# Bypass.net
KiCad netlist of a schematic drawn in Altium Designer
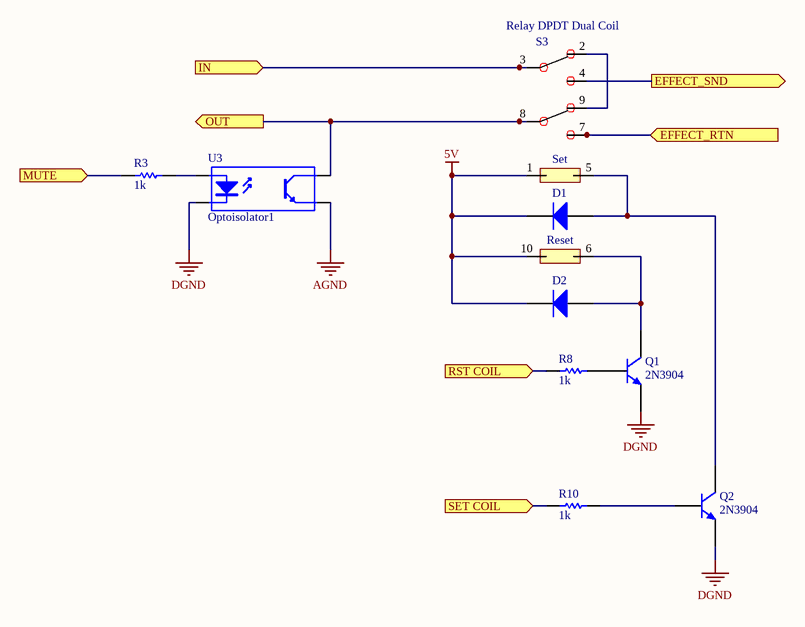
[diagram p0: Bypass.SchDoc]

(export (version "E")
  (design (tool "Eeschema 10.0.6"))
  (components
    (comp (ref "D1")
      (value "Diode 1N4148")
      (footprint "DO-35")
      (description "High Conductance Fast Diode")
      (fields (field (name "PUBLISHER") "Altium Limited"))
      (libsource (lib "Miscellaneous Devices") (part "Diode 1N4148"))
    )
    (comp (ref "D2")
      (value "Diode 1N4148")
      (footprint "DO-35")
      (description "High Conductance Fast Diode")
      (fields (field (name "PUBLISHER") "Altium Limited"))
      (libsource (lib "Miscellaneous Devices") (part "Diode 1N4148"))
    )
    (comp (ref "Q1")
      (value "2N3904")
      (footprint "TO-92A")
      (description "NPN General Purpose Amplifier")
      (fields (field (name "PUBLISHER") "Altium Limited"))
      (libsource (lib "Miscellaneous Devices") (part "2N3904"))
    )
    (comp (ref "Q2")
      (value "2N3904")
      (footprint "TO-92A")
      (description "NPN General Purpose Amplifier")
      (fields (field (name "PUBLISHER") "Altium Limited"))
      (libsource (lib "Miscellaneous Devices") (part "2N3904"))
    )
    (comp (ref "R3")
      (value "1k")
      (footprint "ERA-0805")
      (fields (field (name "PUBLISHER") "Altium Limited"))
      (libsource (lib "Panasonic Resistor") (part "ERAS"))
    )
    (comp (ref "R8")
      (value "1k")
      (footprint "ERA-0805")
      (fields (field (name "PUBLISHER") "Altium Limited"))
      (libsource (lib "Panasonic Resistor") (part "ERAS"))
    )
    (comp (ref "R10")
      (value "1k")
      (footprint "ERA-0805")
      (fields (field (name "PUBLISHER") "Altium Limited"))
      (libsource (lib "Panasonic Resistor") (part "ERAS"))
    )
    (comp (ref "S3")
      (value "Relay DPDT Dual Coil")
      (footprint "EB2 Relay")
      (libsource (lib "Parts") (part "Relay DPDT Dual Coil"))
    )
    (comp (ref "U3")
      (value "Optoisolator1")
      (footprint "DIP-4")
      (description "4-Pin Phototransistor Optocoupler")
      (fields (field (name "PUBLISHER") "Altium Limited"))
      (libsource (lib "Miscellaneous Devices") (part "Optoisolator1"))
    )
  )
  (nets
    (net (code "1") (name "/EFFECT_RTN") (class "Default")
      (node (ref "S3") (pin "7") (pinfunction "7_7") (pintype "passive"))
    )
    (net (code "2") (name "/EFFECT_SND") (class "Default")
      (node (ref "S3") (pin "4") (pinfunction "4_4") (pintype "passive"))
    )
    (net (code "3") (name "/IN") (class "Default")
      (node (ref "S3") (pin "3") (pinfunction "3_3") (pintype "passive"))
    )
    (net (code "4") (name "/MUTE") (class "Default")
      (node (ref "R3") (pin "2") (pinfunction "2_2") (pintype "passive"))
    )
    (net (code "5") (name "/OUT") (class "Default")
      (node (ref "S3") (pin "8") (pinfunction "8_8") (pintype "passive"))
      (node (ref "U3") (pin "4") (pinfunction "C_4") (pintype "passive"))
    )
    (net (code "6") (name "/RST COIL") (class "Default")
      (node (ref "R8") (pin "2") (pinfunction "2_2") (pintype "passive"))
    )
    (net (code "7") (name "/SET COIL") (class "Default")
      (node (ref "R10") (pin "2") (pinfunction "2_2") (pintype "passive"))
    )
    (net (code "8") (name "5V") (class "Default")
      (node (ref "D1") (pin "2") (pinfunction "K_2") (pintype "passive"))
      (node (ref "D2") (pin "2") (pinfunction "K_2") (pintype "passive"))
      (node (ref "S3") (pin "1") (pinfunction "1_1") (pintype "passive"))
      (node (ref "S3") (pin "10") (pinfunction "10_10") (pintype "passive"))
    )
    (net (code "9") (name "AGND") (class "Default")
      (node (ref "U3") (pin "3") (pinfunction "E_3") (pintype "passive"))
    )
    (net (code "10") (name "DGND") (class "Default")
      (node (ref "Q1") (pin "1") (pinfunction "E_1") (pintype "passive"))
      (node (ref "Q2") (pin "1") (pinfunction "E_1") (pintype "passive"))
      (node (ref "U3") (pin "2") (pinfunction "K_2") (pintype "passive"))
    )
    (net (code "11") (name "Net-(D1-A)") (class "Default")
      (node (ref "D1") (pin "1") (pinfunction "A_1") (pintype "passive"))
      (node (ref "Q2") (pin "3") (pinfunction "C_3") (pintype "passive"))
      (node (ref "S3") (pin "5") (pinfunction "5_5") (pintype "passive"))
    )
    (net (code "12") (name "Net-(D2-A)") (class "Default")
      (node (ref "D2") (pin "1") (pinfunction "A_1") (pintype "passive"))
      (node (ref "Q1") (pin "3") (pinfunction "C_3") (pintype "passive"))
      (node (ref "S3") (pin "6") (pinfunction "6_6") (pintype "passive"))
    )
    (net (code "13") (name "Net-(Q1-B)") (class "Default")
      (node (ref "Q1") (pin "2") (pinfunction "B_2") (pintype "passive"))
      (node (ref "R8") (pin "1") (pinfunction "1_1") (pintype "passive"))
    )
    (net (code "14") (name "Net-(Q2-B)") (class "Default")
      (node (ref "Q2") (pin "2") (pinfunction "B_2") (pintype "passive"))
      (node (ref "R10") (pin "1") (pinfunction "1_1") (pintype "passive"))
    )
    (net (code "15") (name "Net-(S3-Pad2)") (class "Default")
      (node (ref "S3") (pin "2") (pinfunction "2_2") (pintype "passive"))
      (node (ref "S3") (pin "9") (pinfunction "9_9") (pintype "passive"))
    )
    (net (code "16") (name "Net-(U3-A)") (class "Default")
      (node (ref "R3") (pin "1") (pinfunction "1_1") (pintype "passive"))
      (node (ref "U3") (pin "1") (pinfunction "A_1") (pintype "passive"))
    )
  )
)
